# P03_Connectors.net
KiCad netlist of a schematic drawn in Altium Designer
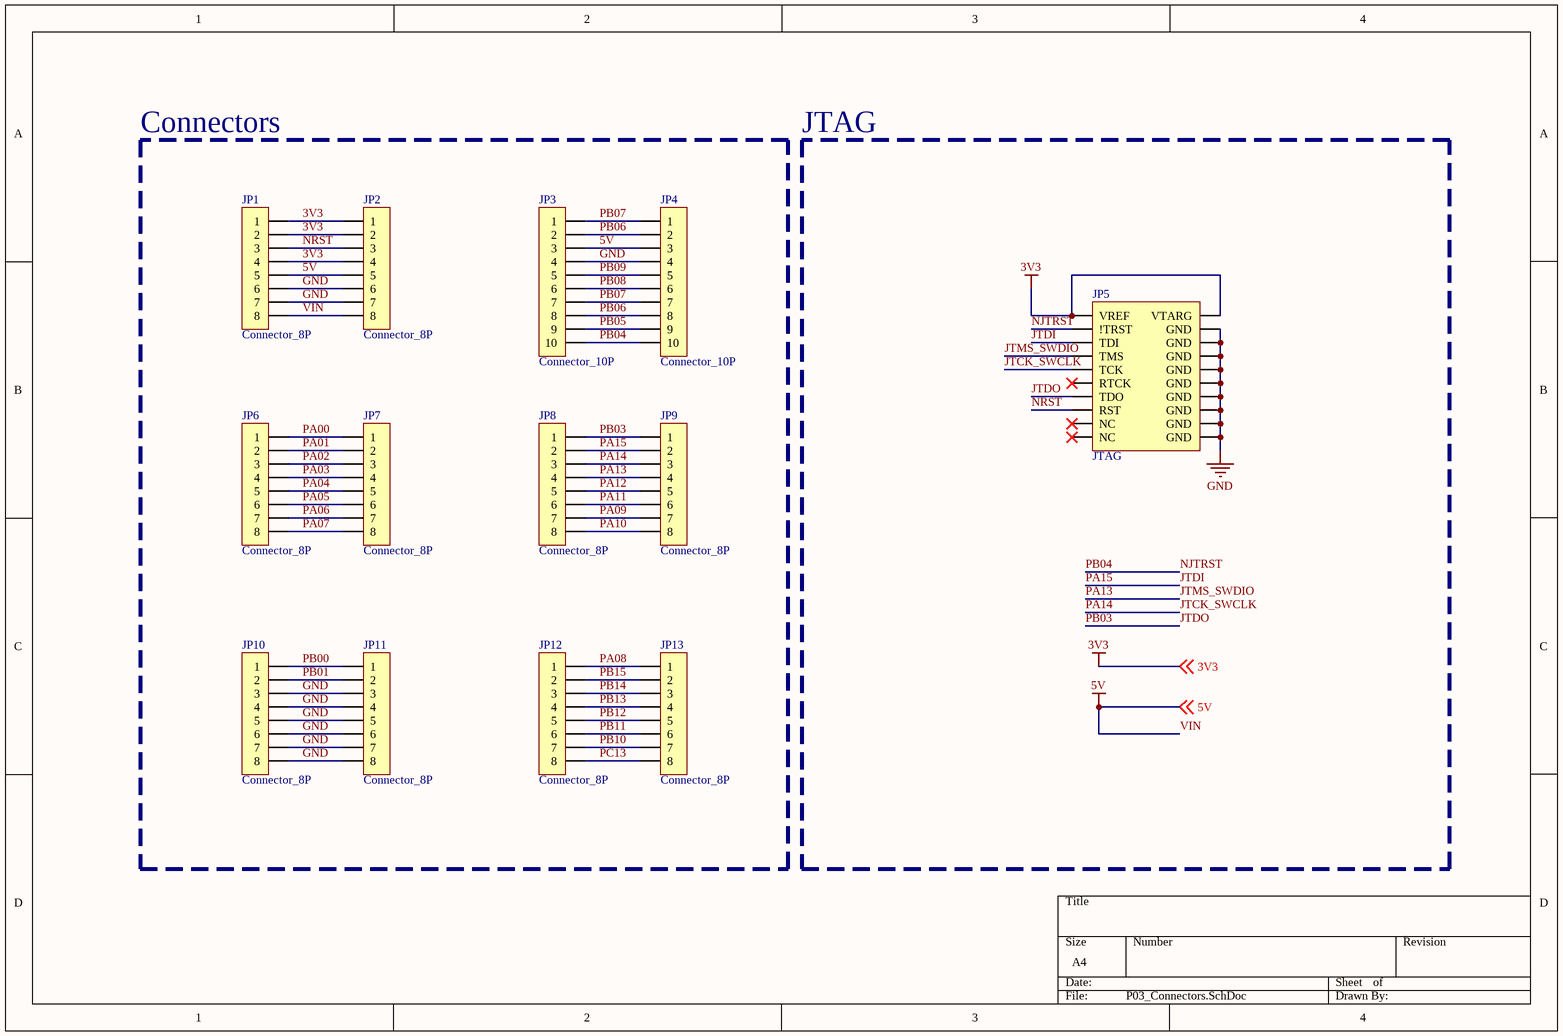
[diagram p0: P03_Connectors.SchDoc]

(export (version "E")
  (design (tool "Eeschema 10.0.6"))
  (components
    (comp (ref "JP1")
      (value "Connector_8P")
      (footprint "排母_2.54mm_8P")
      (libsource (lib "") (part "Connector_8P_1"))
    )
    (comp (ref "JP2")
      (value "Connector_8P")
      (footprint "排针_2.54mm_8P")
      (libsource (lib "Schlib") (part "Connector_8P"))
    )
    (comp (ref "JP3")
      (value "Connector_10P")
      (footprint "排母_2.54mm_10P")
      (libsource (lib "") (part "Connector_10P_1"))
    )
    (comp (ref "JP4")
      (value "Connector_10P")
      (footprint "排针_2.54mm_10P")
      (libsource (lib "Schlib") (part "Connector_10P"))
    )
    (comp (ref "JP5") (value "JTAG") (footprint "JTAG") (libsource (lib "Schlib") (part "JTAG")))
    (comp (ref "JP6")
      (value "Connector_8P")
      (footprint "排母_2.54mm_8P")
      (libsource (lib "") (part "Connector_8P_1"))
    )
    (comp (ref "JP7")
      (value "Connector_8P")
      (footprint "排针_2.54mm_8P")
      (libsource (lib "Schlib") (part "Connector_8P"))
    )
    (comp (ref "JP8")
      (value "Connector_8P")
      (footprint "排母_2.54mm_8P")
      (libsource (lib "") (part "Connector_8P_1"))
    )
    (comp (ref "JP9")
      (value "Connector_8P")
      (footprint "排针_2.54mm_8P")
      (libsource (lib "Schlib") (part "Connector_8P"))
    )
    (comp (ref "JP10")
      (value "Connector_8P")
      (footprint "排母_2.54mm_8P")
      (libsource (lib "") (part "Connector_8P_1"))
    )
    (comp (ref "JP11")
      (value "Connector_8P")
      (footprint "排针_2.54mm_8P")
      (libsource (lib "Schlib") (part "Connector_8P"))
    )
    (comp (ref "JP12")
      (value "Connector_8P")
      (footprint "排母_2.54mm_8P")
      (libsource (lib "") (part "Connector_8P_1"))
    )
    (comp (ref "JP13")
      (value "Connector_8P")
      (footprint "排针_2.54mm_8P")
      (libsource (lib "Schlib") (part "Connector_8P"))
    )
  )
  (nets
    (net (code "1") (name "/JTCK_SWCLK") (class "Default")
      (node (ref "JP5") (pin "9") (pinfunction "TCK_9") (pintype "passive"))
      (node (ref "JP8") (pin "3") (pinfunction "3_3") (pintype "passive"))
      (node (ref "JP9") (pin "3") (pinfunction "3_3") (pintype "passive"))
    )
    (net (code "2") (name "/JTDI") (class "Default")
      (node (ref "JP5") (pin "5") (pinfunction "TDI_5") (pintype "passive"))
      (node (ref "JP8") (pin "2") (pinfunction "2_2") (pintype "passive"))
      (node (ref "JP9") (pin "2") (pinfunction "2_2") (pintype "passive"))
    )
    (net (code "3") (name "/JTDO") (class "Default")
      (node (ref "JP5") (pin "13") (pinfunction "TDO_13") (pintype "passive"))
      (node (ref "JP8") (pin "1") (pinfunction "1_1") (pintype "passive"))
      (node (ref "JP9") (pin "1") (pinfunction "1_1") (pintype "passive"))
    )
    (net (code "4") (name "/JTMS_SWDIO") (class "Default")
      (node (ref "JP5") (pin "7") (pinfunction "TMS_7") (pintype "passive"))
      (node (ref "JP8") (pin "4") (pinfunction "4_4") (pintype "passive"))
      (node (ref "JP9") (pin "4") (pinfunction "4_4") (pintype "passive"))
    )
    (net (code "5") (name "/NJTRST") (class "Default")
      (node (ref "JP3") (pin "10") (pinfunction "10_10") (pintype "passive"))
      (node (ref "JP4") (pin "10") (pinfunction "10_10") (pintype "passive"))
      (node (ref "JP5") (pin "3") (pinfunction "!TRST_3") (pintype "passive"))
    )
    (net (code "6") (name "/NRST") (class "Default")
      (node (ref "JP1") (pin "3") (pinfunction "3_3") (pintype "passive"))
      (node (ref "JP2") (pin "3") (pinfunction "3_3") (pintype "passive"))
      (node (ref "JP5") (pin "15") (pinfunction "RST_15") (pintype "passive"))
    )
    (net (code "7") (name "/PA00") (class "Default")
      (node (ref "JP6") (pin "1") (pinfunction "1_1") (pintype "passive"))
      (node (ref "JP7") (pin "1") (pinfunction "1_1") (pintype "passive"))
    )
    (net (code "8") (name "/PA01") (class "Default")
      (node (ref "JP6") (pin "2") (pinfunction "2_2") (pintype "passive"))
      (node (ref "JP7") (pin "2") (pinfunction "2_2") (pintype "passive"))
    )
    (net (code "9") (name "/PA02") (class "Default")
      (node (ref "JP6") (pin "3") (pinfunction "3_3") (pintype "passive"))
      (node (ref "JP7") (pin "3") (pinfunction "3_3") (pintype "passive"))
    )
    (net (code "10") (name "/PA03") (class "Default")
      (node (ref "JP6") (pin "4") (pinfunction "4_4") (pintype "passive"))
      (node (ref "JP7") (pin "4") (pinfunction "4_4") (pintype "passive"))
    )
    (net (code "11") (name "/PA04") (class "Default")
      (node (ref "JP6") (pin "5") (pinfunction "5_5") (pintype "passive"))
      (node (ref "JP7") (pin "5") (pinfunction "5_5") (pintype "passive"))
    )
    (net (code "12") (name "/PA05") (class "Default")
      (node (ref "JP6") (pin "6") (pinfunction "6_6") (pintype "passive"))
      (node (ref "JP7") (pin "6") (pinfunction "6_6") (pintype "passive"))
    )
    (net (code "13") (name "/PA06") (class "Default")
      (node (ref "JP6") (pin "7") (pinfunction "7_7") (pintype "passive"))
      (node (ref "JP7") (pin "7") (pinfunction "7_7") (pintype "passive"))
    )
    (net (code "14") (name "/PA07") (class "Default")
      (node (ref "JP6") (pin "8") (pinfunction "8_8") (pintype "passive"))
      (node (ref "JP7") (pin "8") (pinfunction "8_8") (pintype "passive"))
    )
    (net (code "15") (name "/PA08") (class "Default")
      (node (ref "JP12") (pin "1") (pinfunction "1_1") (pintype "passive"))
      (node (ref "JP13") (pin "1") (pinfunction "1_1") (pintype "passive"))
    )
    (net (code "16") (name "/PA09") (class "Default")
      (node (ref "JP8") (pin "7") (pinfunction "7_7") (pintype "passive"))
      (node (ref "JP9") (pin "7") (pinfunction "7_7") (pintype "passive"))
    )
    (net (code "17") (name "/PA10") (class "Default")
      (node (ref "JP8") (pin "8") (pinfunction "8_8") (pintype "passive"))
      (node (ref "JP9") (pin "8") (pinfunction "8_8") (pintype "passive"))
    )
    (net (code "18") (name "/PA11") (class "Default")
      (node (ref "JP8") (pin "6") (pinfunction "6_6") (pintype "passive"))
      (node (ref "JP9") (pin "6") (pinfunction "6_6") (pintype "passive"))
    )
    (net (code "19") (name "/PA12") (class "Default")
      (node (ref "JP8") (pin "5") (pinfunction "5_5") (pintype "passive"))
      (node (ref "JP9") (pin "5") (pinfunction "5_5") (pintype "passive"))
    )
    (net (code "20") (name "/PB00") (class "Default")
      (node (ref "JP10") (pin "1") (pinfunction "1_1") (pintype "passive"))
      (node (ref "JP11") (pin "1") (pinfunction "1_1") (pintype "passive"))
    )
    (net (code "21") (name "/PB01") (class "Default")
      (node (ref "JP10") (pin "2") (pinfunction "2_2") (pintype "passive"))
      (node (ref "JP11") (pin "2") (pinfunction "2_2") (pintype "passive"))
    )
    (net (code "22") (name "/PB05") (class "Default")
      (node (ref "JP3") (pin "9") (pinfunction "9_9") (pintype "passive"))
      (node (ref "JP4") (pin "9") (pinfunction "9_9") (pintype "passive"))
    )
    (net (code "23") (name "/PB06") (class "Default")
      (node (ref "JP3") (pin "2") (pinfunction "2_2") (pintype "passive"))
      (node (ref "JP3") (pin "8") (pinfunction "8_8") (pintype "passive"))
      (node (ref "JP4") (pin "2") (pinfunction "2_2") (pintype "passive"))
      (node (ref "JP4") (pin "8") (pinfunction "8_8") (pintype "passive"))
    )
    (net (code "24") (name "/PB07") (class "Default")
      (node (ref "JP3") (pin "1") (pinfunction "1_1") (pintype "passive"))
      (node (ref "JP3") (pin "7") (pinfunction "7_7") (pintype "passive"))
      (node (ref "JP4") (pin "1") (pinfunction "1_1") (pintype "passive"))
      (node (ref "JP4") (pin "7") (pinfunction "7_7") (pintype "passive"))
    )
    (net (code "25") (name "/PB08") (class "Default")
      (node (ref "JP3") (pin "6") (pinfunction "6_6") (pintype "passive"))
      (node (ref "JP4") (pin "6") (pinfunction "6_6") (pintype "passive"))
    )
    (net (code "26") (name "/PB09") (class "Default")
      (node (ref "JP3") (pin "5") (pinfunction "5_5") (pintype "passive"))
      (node (ref "JP4") (pin "5") (pinfunction "5_5") (pintype "passive"))
    )
    (net (code "27") (name "/PB10") (class "Default")
      (node (ref "JP12") (pin "7") (pinfunction "7_7") (pintype "passive"))
      (node (ref "JP13") (pin "7") (pinfunction "7_7") (pintype "passive"))
    )
    (net (code "28") (name "/PB11") (class "Default")
      (node (ref "JP12") (pin "6") (pinfunction "6_6") (pintype "passive"))
      (node (ref "JP13") (pin "6") (pinfunction "6_6") (pintype "passive"))
    )
    (net (code "29") (name "/PB12") (class "Default")
      (node (ref "JP12") (pin "5") (pinfunction "5_5") (pintype "passive"))
      (node (ref "JP13") (pin "5") (pinfunction "5_5") (pintype "passive"))
    )
    (net (code "30") (name "/PB13") (class "Default")
      (node (ref "JP12") (pin "4") (pinfunction "4_4") (pintype "passive"))
      (node (ref "JP13") (pin "4") (pinfunction "4_4") (pintype "passive"))
    )
    (net (code "31") (name "/PB14") (class "Default")
      (node (ref "JP12") (pin "3") (pinfunction "3_3") (pintype "passive"))
      (node (ref "JP13") (pin "3") (pinfunction "3_3") (pintype "passive"))
    )
    (net (code "32") (name "/PB15") (class "Default")
      (node (ref "JP12") (pin "2") (pinfunction "2_2") (pintype "passive"))
      (node (ref "JP13") (pin "2") (pinfunction "2_2") (pintype "passive"))
    )
    (net (code "33") (name "/PC13") (class "Default")
      (node (ref "JP12") (pin "8") (pinfunction "8_8") (pintype "passive"))
      (node (ref "JP13") (pin "8") (pinfunction "8_8") (pintype "passive"))
    )
    (net (code "34") (name "3V3") (class "Default")
      (node (ref "JP1") (pin "1") (pinfunction "1_1") (pintype "passive"))
      (node (ref "JP1") (pin "2") (pinfunction "2_2") (pintype "passive"))
      (node (ref "JP1") (pin "4") (pinfunction "4_4") (pintype "passive"))
      (node (ref "JP2") (pin "1") (pinfunction "1_1") (pintype "passive"))
      (node (ref "JP2") (pin "2") (pinfunction "2_2") (pintype "passive"))
      (node (ref "JP2") (pin "4") (pinfunction "4_4") (pintype "passive"))
      (node (ref "JP5") (pin "1") (pinfunction "VREF_1") (pintype "passive"))
      (node (ref "JP5") (pin "2") (pinfunction "VTARG_2") (pintype "passive"))
    )
    (net (code "35") (name "5V") (class "Default")
      (node (ref "JP1") (pin "5") (pinfunction "5_5") (pintype "passive"))
      (node (ref "JP1") (pin "8") (pinfunction "8_8") (pintype "passive"))
      (node (ref "JP2") (pin "5") (pinfunction "5_5") (pintype "passive"))
      (node (ref "JP2") (pin "8") (pinfunction "8_8") (pintype "passive"))
      (node (ref "JP3") (pin "3") (pinfunction "3_3") (pintype "passive"))
      (node (ref "JP4") (pin "3") (pinfunction "3_3") (pintype "passive"))
    )
    (net (code "36") (name "GND") (class "Default")
      (node (ref "JP1") (pin "6") (pinfunction "6_6") (pintype "passive"))
      (node (ref "JP1") (pin "7") (pinfunction "7_7") (pintype "passive"))
      (node (ref "JP10") (pin "3") (pinfunction "3_3") (pintype "passive"))
      (node (ref "JP10") (pin "4") (pinfunction "4_4") (pintype "passive"))
      (node (ref "JP10") (pin "5") (pinfunction "5_5") (pintype "passive"))
      (node (ref "JP10") (pin "6") (pinfunction "6_6") (pintype "passive"))
      (node (ref "JP10") (pin "7") (pinfunction "7_7") (pintype "passive"))
      (node (ref "JP10") (pin "8") (pinfunction "8_8") (pintype "passive"))
      (node (ref "JP11") (pin "3") (pinfunction "3_3") (pintype "passive"))
      (node (ref "JP11") (pin "4") (pinfunction "4_4") (pintype "passive"))
      (node (ref "JP11") (pin "5") (pinfunction "5_5") (pintype "passive"))
      (node (ref "JP11") (pin "6") (pinfunction "6_6") (pintype "passive"))
      (node (ref "JP11") (pin "7") (pinfunction "7_7") (pintype "passive"))
      (node (ref "JP11") (pin "8") (pinfunction "8_8") (pintype "passive"))
      (node (ref "JP2") (pin "6") (pinfunction "6_6") (pintype "passive"))
      (node (ref "JP2") (pin "7") (pinfunction "7_7") (pintype "passive"))
      (node (ref "JP3") (pin "4") (pinfunction "4_4") (pintype "passive"))
      (node (ref "JP4") (pin "4") (pinfunction "4_4") (pintype "passive"))
      (node (ref "JP5") (pin "10") (pinfunction "GND_10") (pintype "passive"))
      (node (ref "JP5") (pin "12") (pinfunction "GND_12") (pintype "passive"))
      (node (ref "JP5") (pin "14") (pinfunction "GND_14") (pintype "passive"))
      (node (ref "JP5") (pin "16") (pinfunction "GND_16") (pintype "passive"))
      (node (ref "JP5") (pin "18") (pinfunction "GND_18") (pintype "passive"))
      (node (ref "JP5") (pin "20") (pinfunction "GND_20") (pintype "passive"))
      (node (ref "JP5") (pin "4") (pinfunction "GND_4") (pintype "passive"))
      (node (ref "JP5") (pin "6") (pinfunction "GND_6") (pintype "passive"))
      (node (ref "JP5") (pin "8") (pinfunction "GND_8") (pintype "passive"))
    )
    (net (code "37") (name "unconnected-(JP5-NC-Pad17)") (class "Default")
      (node (ref "JP5") (pin "17") (pinfunction "NC_17") (pintype "passive+no_connect"))
    )
    (net (code "38") (name "unconnected-(JP5-NC-Pad19)") (class "Default")
      (node (ref "JP5") (pin "19") (pinfunction "NC_19") (pintype "passive+no_connect"))
    )
    (net (code "39") (name "unconnected-(JP5-RTCK-Pad11)") (class "Default")
      (node (ref "JP5") (pin "11") (pinfunction "RTCK_11") (pintype "passive+no_connect"))
    )
  )
)
